# 41-SoC_POWER_SUPPLY.net
KiCad netlist of a schematic drawn in Altium Designer
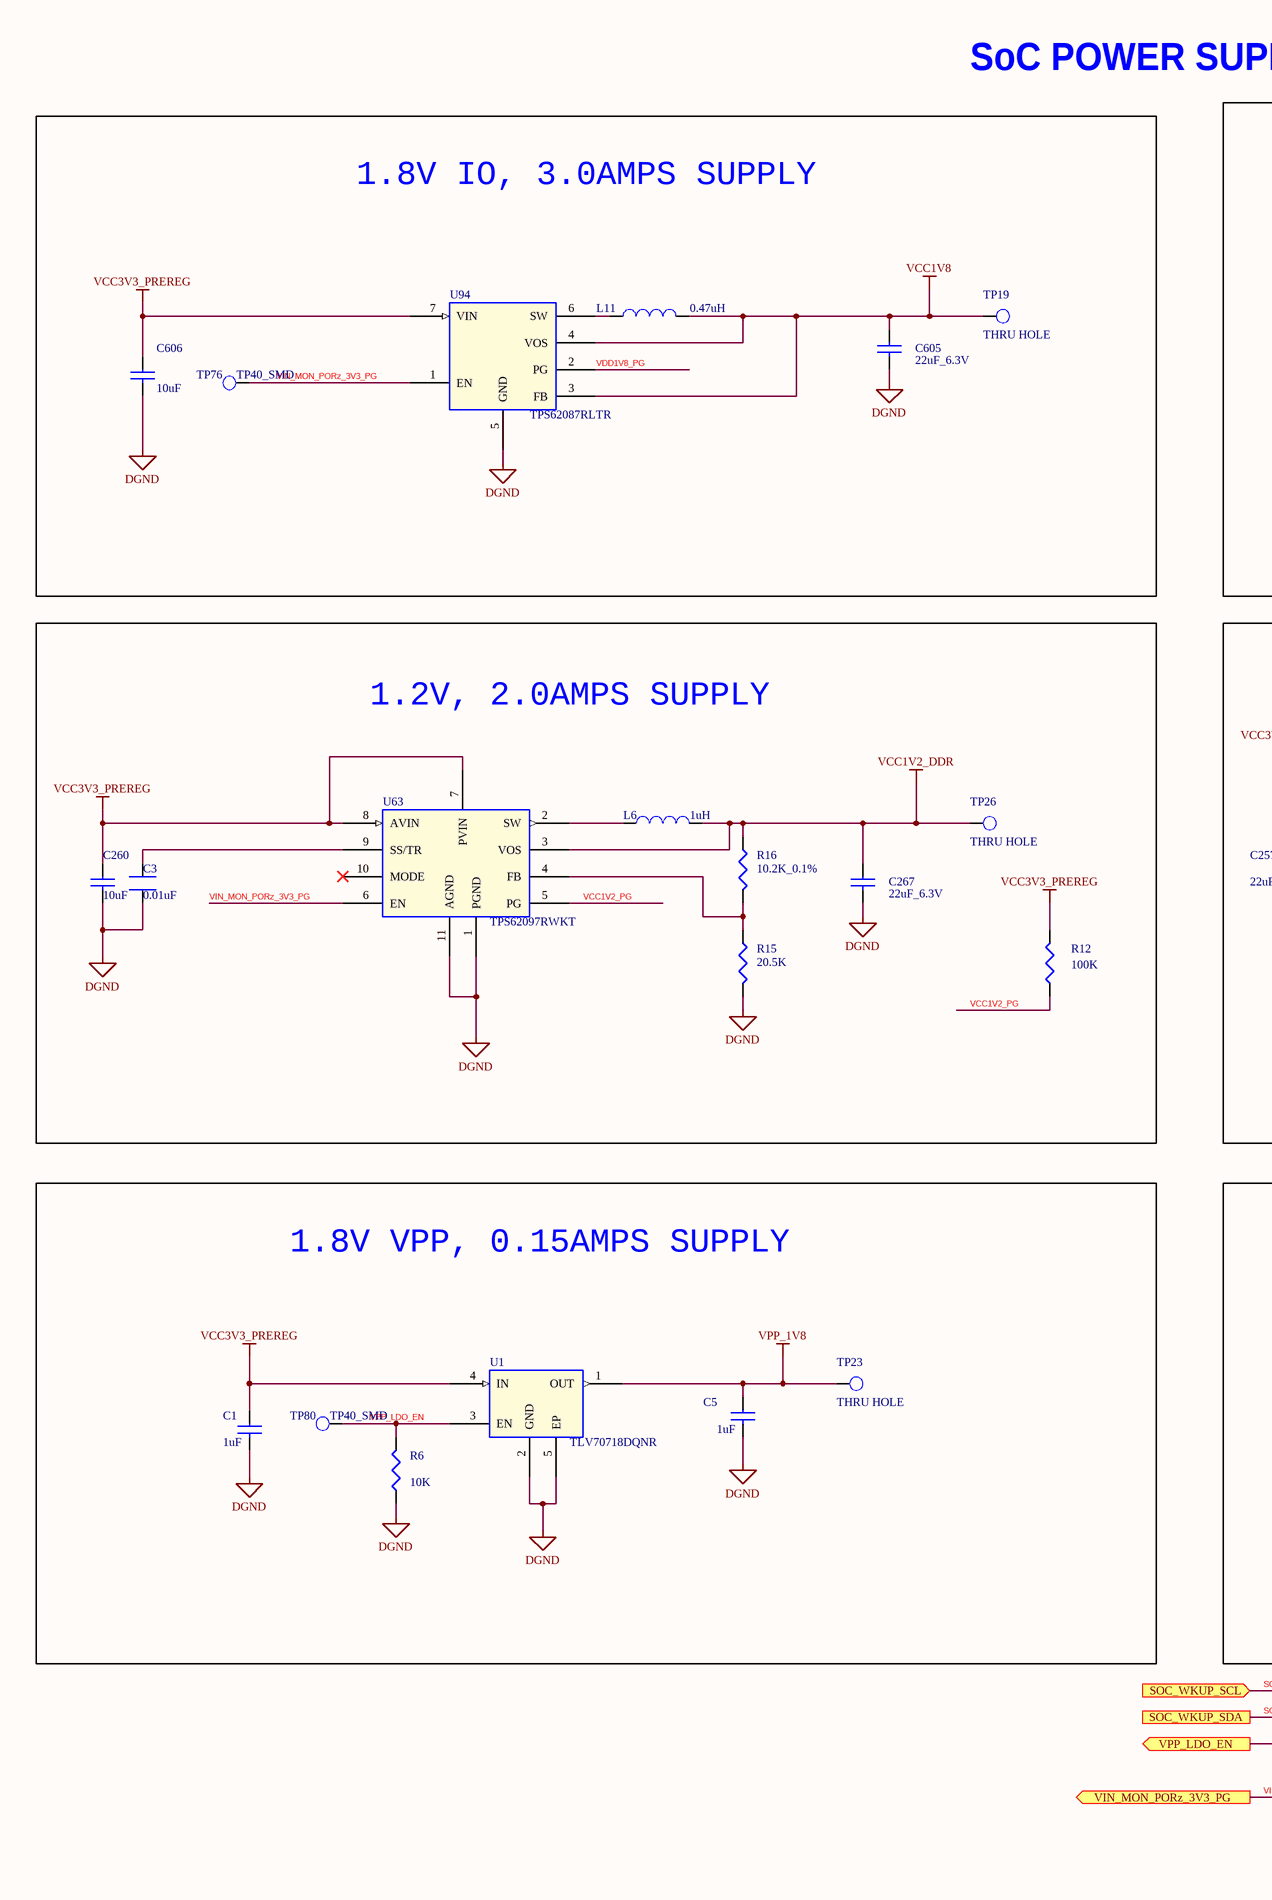
[diagram p0: 41-SoC POWER SUPPLY.SchDoc, left]
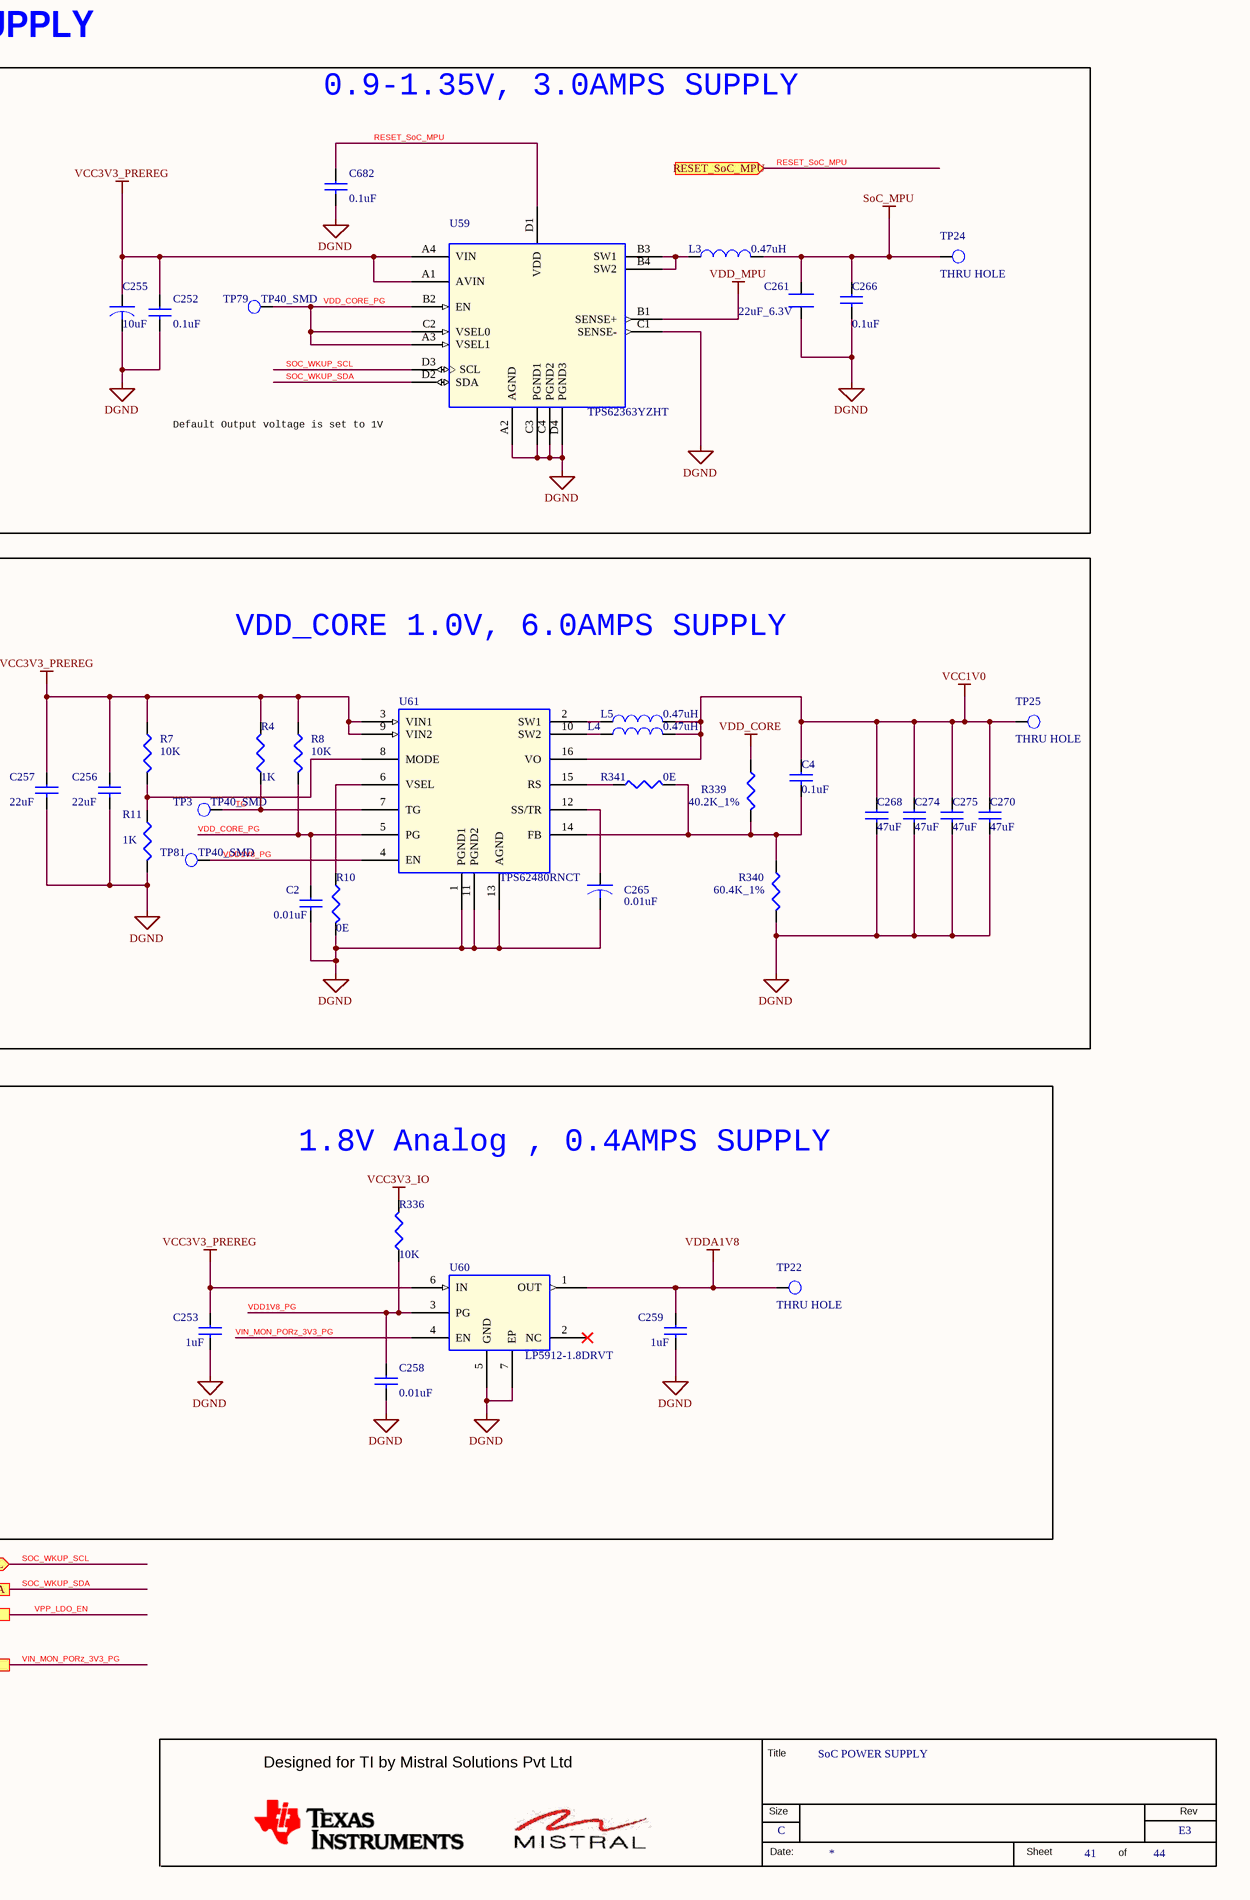
[diagram p1: 41-SoC POWER SUPPLY.SchDoc, right]

(export (version "E")
  (design (tool "Eeschema 10.0.6"))
  (components
    (comp (ref "C1")
      (value "1uF")
      (footprint "CAP0603_1")
      (description "CAP CERAMIC 1uF 25V 10% X5R 0603")
      (fields
        (field (name "MISTRAL PART NO") "120010080040-R")
        (field (name "MFR_PART_NUMBER") "06033D105KAT2A")
      )
      (libsource (lib "*") (part "CAP_Dup5"))
    )
    (comp (ref "C2")
      (value "0.01uF")
      (footprint "CAP0201_0-5")
      (description "CAP CERAMIC 0.01uF 25V 10% X5R 0201")
      (fields
        (field (name "MISTRAL PART NO") "120018010007-R")
        (field (name "MFR_PART_NUMBER") "GRM033R61E103KA12J")
      )
      (libsource (lib "*") (part "CAP_Dup5"))
    )
    (comp (ref "C3")
      (value "0.01uF")
      (footprint "TMDX654GPEVM_BRD:CAP0201_0-5")
      (description "CAP CERAMIC 0.01uF 25V 10% X5R 0201")
      (fields (field (name "DISTRIBUTOR_PART_NUMBER") "GRM033R61E103KA12J-ND") (field (name "VOLTAGE") "25V"))
      (libsource (lib "*") (part "CAP_Dup3"))
    )
    (comp (ref "C4")
      (value "0.1uF")
      (footprint "CAP0201_0-5")
      (description "CAP CERAMIC 0.1uF 16V 10% X5R 0201")
      (fields (field (name "DISTRIBUTOR_PART_NUMBER") "490-16742-1-ND") (field (name "VOLTAGE") "16V"))
      (libsource (lib "*") (part "CAP_Dup5"))
    )
    (comp (ref "C5")
      (value "1uF")
      (footprint "CAP0603_1")
      (description "CAP CERAMIC 1uF 25V 10% X5R 0603")
      (fields
        (field (name "MISTRAL PART NO") "120010080040-R")
        (field (name "MFR_PART_NUMBER") "06033D105KAT2A")
      )
      (libsource (lib "*") (part "CAP_Dup5"))
    )
    (comp (ref "C252")
      (value "0.1uF")
      (footprint "CAP0201_0-5")
      (description "CAP CERAMIC 0.1uF 16V 10% X5R 0201")
      (fields (field (name "DISTRIBUTOR_PART_NUMBER") "490-16742-1-ND") (field (name "VOLTAGE") "16V"))
      (libsource (lib "*") (part "CAP_Dup5"))
    )
    (comp (ref "C253")
      (value "1uF")
      (footprint "CAP0603_1")
      (description "CAP CERAMIC 1uF 25V 10% X5R 0603")
      (fields
        (field (name "MISTRAL PART NO") "120010080040-R")
        (field (name "MFR_PART_NUMBER") "06033D105KAT2A")
      )
      (libsource (lib "*") (part "CAP_Dup5"))
    )
    (comp (ref "C255")
      (value "10uF")
      (footprint "CAP1206_2")
      (description "CAP CERAMIC 10uF 50V 20% X5R 1206")
      (fields (field (name "DISTRIBUTOR_PART_NUMBER") "490-10756-1-ND") (field (name "VOLTAGE") "50V"))
      (libsource (lib "*") (part "CAP"))
    )
    (comp (ref "C256")
      (value "22uF")
      (footprint "CAP1206_2")
      (description "CAP CERAMIC 22uF 16V 20% X7R 1206")
      (fields
        (field (name "MISTRAL PART NO") "120017010003-R")
        (field (name "MFR_PART_NUMBER") "EMK316BB7226ML-T")
      )
      (libsource (lib "*") (part "CAP_Dup5"))
    )
    (comp (ref "C257")
      (value "22uF")
      (footprint "CAP1206_2")
      (description "CAP CERAMIC 22uF 16V 20% X7R 1206")
      (fields
        (field (name "MISTRAL PART NO") "120017010003-R")
        (field (name "MFR_PART_NUMBER") "EMK316BB7226ML-T")
      )
      (libsource (lib "*") (part "CAP_Dup5"))
    )
    (comp (ref "C258")
      (value "0.01uF")
      (footprint "CAP0201_0-5")
      (description "CAP CERAMIC 0.01uF 25V 10% X5R 0201")
      (fields (field (name "DISTRIBUTOR_PART_NUMBER") "GRM033R61E103KA12J-ND") (field (name "VOLTAGE") "25V"))
      (libsource (lib "*") (part "CAP_Dup5"))
    )
    (comp (ref "C259")
      (value "1uF")
      (footprint "CAP0603_1")
      (description "CAP CERAMIC 1uF 25V 10% X5R 0603")
      (fields
        (field (name "MISTRAL PART NO") "120010080040-R")
        (field (name "MFR_PART_NUMBER") "06033D105KAT2A")
      )
      (libsource (lib "*") (part "CAP_Dup5"))
    )
    (comp (ref "C260")
      (value "10uF")
      (footprint "CAP0603_1")
      (description "CAP CERAMIC 10uF 10V 10% X5R 0603")
      (fields
        (field (name "MISTRAL PART NO") "120010080001-R")
        (field (name "MFR_PART_NUMBER") "0603ZD106KAT2A")
      )
      (libsource (lib "*") (part "CAP_Dup5"))
    )
    (comp (ref "C261")
      (value "22uF_6.3V")
      (footprint "TMDX654GPEVM_BRD:CAP0603")
      (description "CAP CERAMIC 22uF 6.3V 20% X5R 0603")
      (fields
        (field (name "MISTRAL PART NO") "120015090007-R")
        (field (name "MFR_PART_NUMBER") "GRM188R60J226MEA0")
      )
      (libsource (lib "*") (part "CAP_Dup3"))
    )
    (comp (ref "C265")
      (value "0.01uF")
      (footprint "CAP0402_0-75")
      (description "CAP CERAMIC 0.01uF 10V 10% X7R 0402")
      (fields
        (field (name "MISTRAL PART NO") "120009030017-R")
        (field (name "MFR_PART_NUMBER") "0402ZC103KAT2A")
      )
      (libsource (lib "*") (part "CAP"))
    )
    (comp (ref "C266")
      (value "0.1uF")
      (footprint "CAP0201_0-5")
      (description "CAP CERAMIC 0.1uF 16V 10% X5R 0201")
      (fields
        (field (name "MISTRAL PART NO") "120009030072-R")
        (field (name "MFR_PART_NUMBER") "GRM033R61C104KE84J")
      )
      (libsource (lib "*") (part "CAP_Dup5"))
    )
    (comp (ref "C267")
      (value "22uF_6.3V")
      (footprint "CAP0603")
      (description "CAP CERAMIC 22uF 6.3V 20% X5R 0603")
      (fields (field (name "DISTRIBUTOR_PART_NUMBER") "490-7611-2-ND") (field (name "VOLTAGE") "6.3V"))
      (libsource (lib "*") (part "CAP_Dup5"))
    )
    (comp (ref "C268")
      (value "47uF")
      (footprint "CAP0603_1")
      (description "CAP CERAMIC 47uF 6.3V 20% X5R 0603")
      (fields (field (name "DISTRIBUTOR_PART_NUMBER") "490-13247-1-ND") (field (name "VOLTAGE") "6.3V"))
      (libsource (lib "*") (part "CAP_Dup5"))
    )
    (comp (ref "C270")
      (value "47uF")
      (footprint "CAP0603_1")
      (description "CAP CERAMIC 47uF 6.3V 20% X5R 0603")
      (fields
        (field (name "MISTRAL PART NO") "120016110001-R")
        (field (name "MFR_PART_NUMBER") "GRM188R60J476ME15D")
      )
      (libsource (lib "*") (part "CAP_Dup5"))
    )
    (comp (ref "C274")
      (value "47uF")
      (footprint "CAP0603_1")
      (description "CAP CERAMIC 47uF 6.3V 20% X5R 0603")
      (fields
        (field (name "MISTRAL PART NO") "120016110001-R")
        (field (name "MFR_PART_NUMBER") "GRM188R60J476ME15D")
      )
      (libsource (lib "*") (part "CAP_Dup5"))
    )
    (comp (ref "C275")
      (value "47uF")
      (footprint "CAP0603_1")
      (description "CAP CERAMIC 47uF 6.3V 20% X5R 0603")
      (fields
        (field (name "MISTRAL PART NO") "120016110001-R")
        (field (name "MFR_PART_NUMBER") "GRM188R60J476ME15D")
      )
      (libsource (lib "*") (part "CAP_Dup5"))
    )
    (comp (ref "C605")
      (value "22uF_6.3V")
      (footprint "CAP0603")
      (description "CAP CERAMIC 22uF 6.3V 20% X5R 0603")
      (fields
        (field (name "MISTRAL PART NO") "120015090007-R")
        (field (name "MFR_PART_NUMBER") "GRM188R60J226MEA0")
      )
      (libsource (lib "*") (part "CAP_Dup5"))
    )
    (comp (ref "C606")
      (value "10uF")
      (footprint "CAP1206_2")
      (description "CAP CERAMIC 10uF 16V 10% X7R 1206")
      (fields
        (field (name "MISTRAL PART NO") "120009090010-R")
        (field (name "MFR_PART_NUMBER") "C1206C106K4RACTU")
      )
      (libsource (lib "*") (part "CAP_Dup5"))
    )
    (comp (ref "C682")
      (value "0.1uF")
      (footprint "CAP0201_0-5")
      (description "CAP CERAMIC 0.1uF 16V 10% X5R 0201")
      (fields (field (name "DISTRIBUTOR_PART_NUMBER") "490-16742-1-ND") (field (name "VOLTAGE") "16V"))
      (libsource (lib "*") (part "CAP_Dup5"))
    )
    (comp (ref "L3")
      (value "0.47uH")
      (footprint "IND_XEL4030_170X170_SMD_1-6")
      (description "IND POWER 0.47uH 20% 11.2A SMD")
      (fields
        (field (name "MISTRAL PART NO") "130018020040-R")
        (field (name "MFR_PART_NUMBER") "XFL4015-471MEB")
      )
      (libsource (lib "*") (part "INDUCTOR"))
    )
    (comp (ref "L4")
      (value "0.47uH")
      (footprint "IND_XEL4030_170X170_SMD_1-6")
      (description "IND POWER 0.47uH 20% 11.2A SMD")
      (fields (field (name "DISTRIBUTOR_PART_NUMBER") "994-XFL4015-471MEB") (field (name "VOLTAGE") "NA"))
      (libsource (lib "*") (part "INDUCTOR"))
    )
    (comp (ref "L5")
      (value "0.47uH")
      (footprint "IND_XEL4030_170X170_SMD_1-6")
      (description "IND POWER 0.47uH 20% 11.2A SMD")
      (fields (field (name "DISTRIBUTOR_PART_NUMBER") "994-XFL4015-471MEB") (field (name "VOLTAGE") "NA"))
      (libsource (lib "*") (part "INDUCTOR"))
    )
    (comp (ref "L6")
      (value "1uH")
      (footprint "IND_IHLP2020AB_210X210_SMD_1-2")
      (description "IND POWER 1uH 4.4A 20% SMD")
      (fields (field (name "DISTRIBUTOR_PART_NUMBER") "541-1704-1-ND") (field (name "VOLTAGE") "NA"))
      (libsource (lib "*") (part "INDUCTOR"))
    )
    (comp (ref "L11")
      (value "0.47uH")
      (footprint "IND_XEL4030_170X170_SMD_1-6")
      (description "IND POWER 0.47uH 20% 11.2A SMD")
      (fields (field (name "DISTRIBUTOR_PART_NUMBER") "994-XFL4015-471MEB") (field (name "VOLTAGE") "NA"))
      (libsource (lib "*") (part "INDUCTOR"))
    )
    (comp (ref "R4")
      (value "1K")
      (footprint "RES0201")
      (description "RES 1K 1/20W 5% 0201")
      (fields
        (field (name "MISTRAL PART NO") "110015080014-R")
        (field (name "MFR_PART_NUMBER") "CRCW02011K00FKED")
      )
      (libsource (lib "*") (part "RESISTOR_Dup4"))
    )
    (comp (ref "R6")
      (value "10K")
      (footprint "RES0402_0-5")
      (description "RES 10K 1/16W 5% 0402")
      (fields (field (name "DISTRIBUTOR_PART_NUMBER") "311-10KJRCT-ND") (field (name "VOLTAGE") "NA"))
      (libsource (lib "*") (part "RESISTOR_Dup5"))
    )
    (comp (ref "R7")
      (value "10K")
      (footprint "RES0402_0-5")
      (description "RES 10K 1/16W 5% 0402")
      (fields (field (name "DISTRIBUTOR_PART_NUMBER") "311-10KJRCT-ND") (field (name "VOLTAGE") "NA"))
      (libsource (lib "*") (part "RESISTOR_Dup5"))
    )
    (comp (ref "R8")
      (value "10K")
      (footprint "RES0402_0-5")
      (description "RES 10K 1/16W 5% 0402")
      (fields
        (field (name "MISTRAL PART NO") "110009030208-R")
        (field (name "MFR_PART_NUMBER") "RC0402JR-0710KL")
      )
      (libsource (lib "*") (part "RESISTOR_Dup5"))
    )
    (comp (ref "R10")
      (value "0E")
      (footprint "RES0402_0-5")
      (description "RES 0E 1/16W 0402")
      (fields (field (name "DISTRIBUTOR_PART_NUMBER") "541-0.0JCT-ND") (field (name "VOLTAGE") "NA"))
      (libsource (lib "*") (part "RESISTOR_Dup5"))
    )
    (comp (ref "R11")
      (value "1K")
      (footprint "RES0201")
      (description "RES 1K 1/20W 5% 0201")
      (fields
        (field (name "MISTRAL PART NO") "110015080014-R")
        (field (name "MFR_PART_NUMBER") "CRCW02011K00FKED")
      )
      (libsource (lib "*") (part "RESISTOR_Dup5"))
    )
    (comp (ref "R12")
      (value "100K")
      (footprint "RES0402_0-5")
      (description "RES 100K 1/16W 5% 0402")
      (fields (field (name "DISTRIBUTOR_PART_NUMBER") "541-100KJCT-ND") (field (name "VOLTAGE") "NA"))
      (libsource (lib "*") (part "RESISTOR_Dup5"))
    )
    (comp (ref "R15")
      (value "20.5K")
      (footprint "RES0402")
      (description "RES 20.5K 1/10W 1% 0402")
      (fields
        (field (name "MISTRAL PART NO") "110010090063-R")
        (field (name "MFR_PART_NUMBER") "ERJ-2RKF2052X")
      )
      (libsource (lib "*") (part "RESISTOR_Dup5"))
    )
    (comp (ref "R16")
      (value "10.2K_0.1%")
      (footprint "RES0402")
      (description "RES 10.2K 1/16W 0.1% 0402")
      (fields
        (field (name "MISTRAL PART NO") "110011050017-R")
        (field (name "MFR_PART_NUMBER") "TNPW040210K2BEED")
      )
      (libsource (lib "*") (part "RESISTOR_Dup5"))
    )
    (comp (ref "R336")
      (value "10K")
      (footprint "RES0402_0-5")
      (description "RES 10K 1/16W 5% 0402")
      (fields
        (field (name "MISTRAL PART NO") "110009030208-R")
        (field (name "MFR_PART_NUMBER") "RC0402JR-0710KL")
      )
      (libsource (lib "*") (part "RESISTOR_Dup5"))
    )
    (comp (ref "R339")
      (value "40.2K_1%")
      (footprint "RES0402_0-5")
      (description "RES 40.2K 1/16W 1% 0402")
      (fields
        (field (name "MISTRAL PART NO") "110009030811")
        (field (name "MFR_PART_NUMBER") "RC0402FR-0740K2L")
      )
      (libsource (lib "*") (part "RESISTOR_Dup5"))
    )
    (comp (ref "R340")
      (value "60.4K_1%")
      (footprint "RES0402_0-5")
      (description "RES 60.4K 1/16W 1% 0402")
      (fields
        (field (name "MISTRAL PART NO") "110012110012-R")
        (field (name "MFR_PART_NUMBER") "RC0402FR-0760K4L")
      )
      (libsource (lib "*") (part "RESISTOR_Dup5"))
    )
    (comp (ref "R341")
      (value "0E")
      (footprint "RES0402_0-5")
      (description "RES 0E 1/16W 0402")
      (fields
        (field (name "MISTRAL PART NO") "110010080019-P")
        (field (name "MFR_PART_NUMBER") "CRCW04020000Z0ED")
      )
      (libsource (lib "*") (part "RESISTOR_Dup5"))
    )
    (comp (ref "TP3")
      (value "TP40_SMD")
      (footprint "TP40_SMD")
      (description "TESTPOINT CIR 40 SMD")
      (fields (field (name "VOLTAGE") "NA") (field (name "MISTRAL PART NO") "130009030933"))
      (libsource (lib "*") (part "TESTPOINT"))
    )
    (comp (ref "TP19")
      (value "THRU HOLE")
      (footprint "TP_40X65")
      (description "TESTPOINT 1.0MM DRILL PTH")
      (fields (field (name "MISTRAL PART NO") "130009030938") (field (name "MFR_PART_NUMBER") "TP_40X65"))
      (libsource (lib "*") (part "TESTPOINT"))
    )
    (comp (ref "TP22")
      (value "THRU HOLE")
      (footprint "TP_40X65")
      (description "TESTPOINT 1.0MM DRILL PTH")
      (fields (field (name "MISTRAL PART NO") "130009030938") (field (name "MFR_PART_NUMBER") "TP_40X65"))
      (libsource (lib "*") (part "TESTPOINT"))
    )
    (comp (ref "TP23")
      (value "THRU HOLE")
      (footprint "TP_40X65")
      (description "TESTPOINT 1.0MM DRILL PTH")
      (fields (field (name "MISTRAL PART NO") "130009030938") (field (name "MFR_PART_NUMBER") "TP_40X65"))
      (libsource (lib "*") (part "TESTPOINT"))
    )
    (comp (ref "TP24")
      (value "THRU HOLE")
      (footprint "TP_40X65")
      (description "TESTPOINT 1.0MM DRILL PTH")
      (fields (field (name "MISTRAL PART NO") "130009030938") (field (name "MFR_PART_NUMBER") "TP_40X65"))
      (libsource (lib "*") (part "TESTPOINT"))
    )
    (comp (ref "TP25")
      (value "THRU HOLE")
      (footprint "TP_40X65")
      (description "TESTPOINT 1.0MM DRILL PTH")
      (fields (field (name "MISTRAL PART NO") "130009030938") (field (name "MFR_PART_NUMBER") "TP_40X65"))
      (libsource (lib "*") (part "TESTPOINT"))
    )
    (comp (ref "TP26")
      (value "THRU HOLE")
      (footprint "TP_40X65")
      (description "TESTPOINT 1.0MM DRILL PTH")
      (fields (field (name "MISTRAL PART NO") "130009030938") (field (name "MFR_PART_NUMBER") "TP_40X65"))
      (libsource (lib "*") (part "TESTPOINT"))
    )
    (comp (ref "TP76")
      (value "TP40_SMD")
      (footprint "TP40_SMD")
      (description "TESTPOINT CIR 40 SMD")
      (fields (field (name "VOLTAGE") "NA") (field (name "MISTRAL PART NO") "130009030933"))
      (libsource (lib "*") (part "TESTPOINT"))
    )
    (comp (ref "TP79")
      (value "TP40_SMD")
      (footprint "TP40_SMD")
      (description "TESTPOINT CIR 40 SMD")
      (fields (field (name "MISTRAL PART NO") "130009030933") (field (name "DISTRIBUTOR_PART_NUMBER") "NA"))
      (libsource (lib "*") (part "TESTPOINT"))
    )
    (comp (ref "TP80")
      (value "TP40_SMD")
      (footprint "TP40_SMD")
      (description "TESTPOINT CIR 40 SMD")
      (fields (field (name "VOLTAGE") "NA") (field (name "MISTRAL PART NO") "130009030933"))
      (libsource (lib "*") (part "TESTPOINT"))
    )
    (comp (ref "TP81")
      (value "TP40_SMD")
      (footprint "TP40_SMD")
      (description "TESTPOINT CIR 40 SMD")
      (fields (field (name "VOLTAGE") "NA") (field (name "MISTRAL PART NO") "130009030933"))
      (libsource (lib "*") (part "TESTPOINT"))
    )
    (comp (ref "U1")
      (value "TLV70718DQNR")
      (footprint "X2SON4_TLV71318P_40X40_0-4")
      (description "IC 200mA LOW IQ LOW NOISE LDO REGULATOR X2SON-4")
      (fields
        (field (name "DISTRIBUTOR_PART_NUMBER") "296-36768-1-ND")
        (field (name "VOLTAGE") "NA")
        (field (name "LIBRARY PATH") "Y~{:}MIS_DATABAS~{E}Librar~{y}ALTIUM_TOO~{L}SCHEMATICS_PART~{S}MS_MISCPOWER_Library.schlib")
      )
      (libsource (lib "*") (part "TLV71318PDQNR_X2SON4"))
    )
    (comp (ref "U59")
      (value "TPS62363YZHT")
      (footprint "DSBGA16_19-68_80X80_0-7")
      (description "IC 3A PROCESSOR SUPPLY WITH I2C INTERFACE DSBGA16")
      (fields (field (name "DISTRIBUTOR_PART_NUMBER") "296-30361-1-ND") (field (name "VOLTAGE") "NA"))
      (libsource (lib "*") (part "TPS6236X_DSBGA16"))
    )
    (comp (ref "U60")
      (value "LP5912-1.8DRVT")
      (footprint "SON6_25-59_85X85_0-8")
      (description "IC 500mA LOW NOISE LOW IQ LDO WSON6")
      (fields (field (name "MISTRAL PART NO") "142017090021-R") (field (name "TOLERANCE") "NA"))
      (libsource (lib "*") (part "LP5912-1-8DRVT_WSON6"))
    )
    (comp (ref "U61")
      (value "TPS62480RNCT")
      (footprint "VQFNHR16_TPS62480_100X120_1")
      (description "IC 2-PHASE STEP DOWN DC-DC CONVERTER VQFN-HR16")
      (fields (field (name "MISTRAL PART NO") "142017090012-R") (field (name "TOLERANCE") "NA"))
      (libsource (lib "*") (part "TPS62480RNCT_VQFNHR16"))
    )
    (comp (ref "U63")
      (value "TPS62097RWKT")
      (footprint "VQFNHR11_TPS62097_80X80_1")
      (description "IC 2A SYNCHRONOUS STEP DOWN CONVERTER WITH IDCS CONTROL VQFN-HR11")
      (fields (field (name "DISTRIBUTOR_PART_NUMBER") "296-43330-1-ND") (field (name "VOLTAGE") "NA"))
      (libsource (lib "*") (part "TPS62097RWKT_VQFNHR11"))
    )
    (comp (ref "U94")
      (value "TPS62087RLTR")
      (footprint "VSONHR7_TPS62085_80X80_1")
      (description "IC 3A STEP DOWN CONVERTER WITH SHORT CIRCUIT PROTECTION VSON-HR7")
      (fields (field (name "DISTRIBUTOR_PART_NUMBER") "296-40832-1-ND") (field (name "VOLTAGE") "NA"))
      (libsource (lib "*") (part "TPS62085RLTR_VSONHR7"))
    )
  )
  (nets
    (net (code "1") (name "/RESET_SoC_MPU") (class "Default")
      (node (ref "C682") (pin "1") (pinfunction "1_1") (pintype "passive"))
      (node (ref "U59") (pin "D1") (pinfunction "VDD_D1") (pintype "power_in"))
    )
    (net (code "2") (name "/SOC_WKUP_SCL") (class "Default")
      (node (ref "U59") (pin "D3") (pinfunction "SCL_D3") (pintype "bidirectional"))
    )
    (net (code "3") (name "/SOC_WKUP_SDA") (class "Default")
      (node (ref "U59") (pin "D2") (pinfunction "SDA_D2") (pintype "bidirectional"))
    )
    (net (code "4") (name "/TG") (class "Default")
      (node (ref "R4") (pin "1") (pinfunction "1_1") (pintype "passive"))
      (node (ref "TP3") (pin "1") (pinfunction "TP_1") (pintype "passive"))
      (node (ref "U61") (pin "7") (pinfunction "TG_7") (pintype "passive"))
    )
    (net (code "5") (name "/VCC1V2_PG") (class "Default")
      (node (ref "R12") (pin "1") (pinfunction "1_1") (pintype "passive"))
      (node (ref "U63") (pin "5") (pinfunction "PG_5") (pintype "passive"))
    )
    (net (code "6") (name "/VDD1V8_PG") (class "Default")
      (node (ref "C258") (pin "1") (pinfunction "1_1") (pintype "passive"))
      (node (ref "R336") (pin "1") (pinfunction "1_1") (pintype "passive"))
      (node (ref "TP81") (pin "1") (pinfunction "TP_1") (pintype "passive"))
      (node (ref "U60") (pin "3") (pinfunction "PG_3") (pintype "passive"))
      (node (ref "U61") (pin "4") (pinfunction "EN_4") (pintype "passive"))
      (node (ref "U94") (pin "2") (pinfunction "PG_2") (pintype "passive"))
    )
    (net (code "7") (name "/VDD_CORE_PG") (class "Default")
      (node (ref "C2") (pin "1") (pinfunction "1_1") (pintype "passive"))
      (node (ref "R8") (pin "2") (pinfunction "2_2") (pintype "passive"))
      (node (ref "TP79") (pin "1") (pinfunction "TP_1") (pintype "passive"))
      (node (ref "U59") (pin "A3") (pinfunction "VSEL1_A3") (pintype "input"))
      (node (ref "U59") (pin "B2") (pinfunction "EN_B2") (pintype "input"))
      (node (ref "U59") (pin "C2") (pinfunction "VSEL0_C2") (pintype "input"))
      (node (ref "U61") (pin "5") (pinfunction "PG_5") (pintype "passive"))
    )
    (net (code "8") (name "/VIN_MON_PORz_3V3_PG") (class "Default")
      (node (ref "TP76") (pin "1") (pinfunction "TP_1") (pintype "passive"))
      (node (ref "U60") (pin "4") (pinfunction "EN_4") (pintype "passive"))
      (node (ref "U63") (pin "6") (pinfunction "EN_6") (pintype "passive"))
      (node (ref "U94") (pin "1") (pinfunction "EN_1") (pintype "passive"))
    )
    (net (code "9") (name "/VPP_LDO_EN") (class "Default")
      (node (ref "R6") (pin "2") (pinfunction "2_2") (pintype "passive"))
      (node (ref "TP80") (pin "1") (pinfunction "TP_1") (pintype "passive"))
      (node (ref "U1") (pin "3") (pinfunction "EN_3") (pintype "passive"))
    )
    (net (code "10") (name "DGND") (class "Default")
      (node (ref "C1") (pin "2") (pinfunction "2_2") (pintype "passive"))
      (node (ref "C2") (pin "2") (pinfunction "2_2") (pintype "passive"))
      (node (ref "C252") (pin "2") (pinfunction "2_2") (pintype "passive"))
      (node (ref "C253") (pin "2") (pinfunction "2_2") (pintype "passive"))
      (node (ref "C255") (pin "2") (pinfunction "2_2") (pintype "passive"))
      (node (ref "C256") (pin "2") (pinfunction "2_2") (pintype "passive"))
      (node (ref "C257") (pin "2") (pinfunction "2_2") (pintype "passive"))
      (node (ref "C258") (pin "2") (pinfunction "2_2") (pintype "passive"))
      (node (ref "C259") (pin "2") (pinfunction "2_2") (pintype "passive"))
      (node (ref "C260") (pin "2") (pinfunction "2_2") (pintype "passive"))
      (node (ref "C261") (pin "2") (pinfunction "2_2") (pintype "passive"))
      (node (ref "C265") (pin "2") (pinfunction "2_2") (pintype "passive"))
      (node (ref "C266") (pin "2") (pinfunction "2_2") (pintype "passive"))
      (node (ref "C267") (pin "2") (pinfunction "2_2") (pintype "passive"))
      (node (ref "C268") (pin "2") (pinfunction "2_2") (pintype "passive"))
      (node (ref "C270") (pin "2") (pinfunction "2_2") (pintype "passive"))
      (node (ref "C274") (pin "2") (pinfunction "2_2") (pintype "passive"))
      (node (ref "C275") (pin "2") (pinfunction "2_2") (pintype "passive"))
      (node (ref "C3") (pin "2") (pinfunction "2_2") (pintype "passive"))
      (node (ref "C5") (pin "2") (pinfunction "2_2") (pintype "passive"))
      (node (ref "C605") (pin "2") (pinfunction "2_2") (pintype "passive"))
      (node (ref "C606") (pin "2") (pinfunction "2_2") (pintype "passive"))
      (node (ref "C682") (pin "2") (pinfunction "2_2") (pintype "passive"))
      (node (ref "R10") (pin "2") (pinfunction "2_2") (pintype "passive"))
      (node (ref "R11") (pin "2") (pinfunction "2_2") (pintype "passive"))
      (node (ref "R15") (pin "2") (pinfunction "2_2") (pintype "passive"))
      (node (ref "R340") (pin "2") (pinfunction "2_2") (pintype "passive"))
      (node (ref "R6") (pin "1") (pinfunction "1_1") (pintype "passive"))
      (node (ref "U1") (pin "2") (pinfunction "GND_2") (pintype "power_in"))
      (node (ref "U1") (pin "5") (pinfunction "EP_5") (pintype "power_in"))
      (node (ref "U59") (pin "A2") (pinfunction "AGND_A2") (pintype "power_in"))
      (node (ref "U59") (pin "C1") (pinfunction "SENSE-_C1") (pintype "output"))
      (node (ref "U59") (pin "C3") (pinfunction "PGND1_C3") (pintype "power_in"))
      (node (ref "U59") (pin "C4") (pinfunction "PGND2_C4") (pintype "power_in"))
      (node (ref "U59") (pin "D4") (pinfunction "PGND3_D4") (pintype "power_in"))
      (node (ref "U60") (pin "5") (pinfunction "GND_5") (pintype "power_in"))
      (node (ref "U60") (pin "7") (pinfunction "EP_7") (pintype "power_in"))
      (node (ref "U61") (pin "1") (pinfunction "PGND1_1") (pintype "power_in"))
      (node (ref "U61") (pin "11") (pinfunction "PGND2_11") (pintype "power_in"))
      (node (ref "U61") (pin "13") (pinfunction "AGND_13") (pintype "power_in"))
      (node (ref "U63") (pin "1") (pinfunction "PGND_1") (pintype "power_in"))
      (node (ref "U63") (pin "11") (pinfunction "AGND_11") (pintype "power_in"))
      (node (ref "U94") (pin "5") (pinfunction "GND_5") (pintype "power_in"))
    )
    (net (code "11") (name "Net-(U59-SW1)") (class "Default")
      (node (ref "L3") (pin "1") (pinfunction "1_1") (pintype "passive"))
      (node (ref "U59") (pin "B3") (pinfunction "SW1_B3") (pintype "passive"))
      (node (ref "U59") (pin "B4") (pinfunction "SW2_B4") (pintype "passive"))
    )
    (net (code "12") (name "Net-(U61-FB)") (class "Default")
      (node (ref "C4") (pin "2") (pinfunction "2_2") (pintype "passive"))
      (node (ref "R339") (pin "2") (pinfunction "2_2") (pintype "passive"))
      (node (ref "R340") (pin "1") (pinfunction "1_1") (pintype "passive"))
      (node (ref "R341") (pin "2") (pinfunction "2_2") (pintype "passive"))
      (node (ref "U61") (pin "14") (pinfunction "FB_14") (pintype "passive"))
    )
    (net (code "13") (name "Net-(U61-MODE)") (class "Default")
      (node (ref "R11") (pin "1") (pinfunction "1_1") (pintype "passive"))
      (node (ref "R7") (pin "2") (pinfunction "2_2") (pintype "passive"))
      (node (ref "U61") (pin "8") (pinfunction "MODE_8") (pintype "passive"))
    )
    (net (code "14") (name "Net-(U61-RS)") (class "Default")
      (node (ref "R341") (pin "1") (pinfunction "1_1") (pintype "passive"))
      (node (ref "U61") (pin "15") (pinfunction "RS_15") (pintype "passive"))
    )
    (net (code "15") (name "Net-(U61-SS{slash}TR)") (class "Default")
      (node (ref "C265") (pin "1") (pinfunction "1_1") (pintype "passive"))
      (node (ref "U61") (pin "12") (pinfunction "SS/TR_12") (pintype "passive"))
    )
    (net (code "16") (name "Net-(U61-SW1)") (class "Default")
      (node (ref "L5") (pin "1") (pinfunction "1_1") (pintype "passive"))
      (node (ref "U61") (pin "2") (pinfunction "SW1_2") (pintype "passive"))
    )
    (net (code "17") (name "Net-(U61-SW2)") (class "Default")
      (node (ref "L4") (pin "1") (pinfunction "1_1") (pintype "passive"))
      (node (ref "U61") (pin "10") (pinfunction "SW2_10") (pintype "passive"))
    )
    (net (code "18") (name "Net-(U61-VSEL)") (class "Default")
      (node (ref "R10") (pin "1") (pinfunction "1_1") (pintype "passive"))
      (node (ref "U61") (pin "6") (pinfunction "VSEL_6") (pintype "passive"))
    )
    (net (code "19") (name "Net-(U63-FB)") (class "Default")
      (node (ref "R15") (pin "1") (pinfunction "1_1") (pintype "passive"))
      (node (ref "R16") (pin "2") (pinfunction "2_2") (pintype "passive"))
      (node (ref "U63") (pin "4") (pinfunction "FB_4") (pintype "passive"))
    )
    (net (code "20") (name "Net-(U63-SS{slash}TR)") (class "Default")
      (node (ref "C3") (pin "1") (pinfunction "1_1") (pintype "passive"))
      (node (ref "U63") (pin "9") (pinfunction "SS/TR_9") (pintype "passive"))
    )
    (net (code "21") (name "Net-(U63-SW)") (class "Default")
      (node (ref "L6") (pin "1") (pinfunction "1_1") (pintype "passive"))
      (node (ref "U63") (pin "2") (pinfunction "SW_2") (pintype "output"))
    )
    (net (code "22") (name "Net-(U94-SW)") (class "Default")
      (node (ref "L11") (pin "1") (pinfunction "1_1") (pintype "passive"))
      (node (ref "U94") (pin "6") (pinfunction "SW_6") (pintype "passive"))
    )
    (net (code "23") (name "SoC_MPU") (class "Default")
      (node (ref "C261") (pin "1") (pinfunction "1_1") (pintype "passive"))
      (node (ref "C266") (pin "1") (pinfunction "1_1") (pintype "passive"))
      (node (ref "L3") (pin "2") (pinfunction "2_2") (pintype "passive"))
      (node (ref "TP24") (pin "1") (pinfunction "TP_1") (pintype "passive"))
    )
    (net (code "24") (name "VCC1V0") (class "Default")
      (node (ref "C268") (pin "1") (pinfunction "1_1") (pintype "passive"))
      (node (ref "C270") (pin "1") (pinfunction "1_1") (pintype "passive"))
      (node (ref "C274") (pin "1") (pinfunction "1_1") (pintype "passive"))
      (node (ref "C275") (pin "1") (pinfunction "1_1") (pintype "passive"))
      (node (ref "C4") (pin "1") (pinfunction "1_1") (pintype "passive"))
      (node (ref "L4") (pin "2") (pinfunction "2_2") (pintype "passive"))
      (node (ref "L5") (pin "2") (pinfunction "2_2") (pintype "passive"))
      (node (ref "TP25") (pin "1") (pinfunction "TP_1") (pintype "passive"))
      (node (ref "U61") (pin "16") (pinfunction "VO_16") (pintype "passive"))
    )
    (net (code "25") (name "VCC1V2_DDR") (class "Default")
      (node (ref "C267") (pin "1") (pinfunction "1_1") (pintype "passive"))
      (node (ref "L6") (pin "2") (pinfunction "2_2") (pintype "passive"))
      (node (ref "R16") (pin "1") (pinfunction "1_1") (pintype "passive"))
      (node (ref "TP26") (pin "1") (pinfunction "TP_1") (pintype "passive"))
      (node (ref "U63") (pin "3") (pinfunction "VOS_3") (pintype "passive"))
    )
    (net (code "26") (name "VCC1V8") (class "Default")
      (node (ref "C605") (pin "1") (pinfunction "1_1") (pintype "passive"))
      (node (ref "L11") (pin "2") (pinfunction "2_2") (pintype "passive"))
      (node (ref "TP19") (pin "1") (pinfunction "TP_1") (pintype "passive"))
      (node (ref "U94") (pin "3") (pinfunction "FB_3") (pintype "passive"))
      (node (ref "U94") (pin "4") (pinfunction "VOS_4") (pintype "passive"))
    )
    (net (code "27") (name "VCC3V3_IO") (class "Default")
      (node (ref "R336") (pin "2") (pinfunction "2_2") (pintype "passive"))
    )
    (net (code "28") (name "VCC3V3_PREREG") (class "Default")
      (node (ref "C1") (pin "1") (pinfunction "1_1") (pintype "passive"))
      (node (ref "C252") (pin "1") (pinfunction "1_1") (pintype "passive"))
      (node (ref "C253") (pin "1") (pinfunction "1_1") (pintype "passive"))
      (node (ref "C255") (pin "1") (pinfunction "1_1") (pintype "passive"))
      (node (ref "C256") (pin "1") (pinfunction "1_1") (pintype "passive"))
      (node (ref "C257") (pin "1") (pinfunction "1_1") (pintype "passive"))
      (node (ref "C260") (pin "1") (pinfunction "1_1") (pintype "passive"))
      (node (ref "C606") (pin "1") (pinfunction "1_1") (pintype "passive"))
      (node (ref "R12") (pin "2") (pinfunction "2_2") (pintype "passive"))
      (node (ref "R4") (pin "2") (pinfunction "2_2") (pintype "passive"))
      (node (ref "R7") (pin "1") (pinfunction "1_1") (pintype "passive"))
      (node (ref "R8") (pin "1") (pinfunction "1_1") (pintype "passive"))
      (node (ref "U1") (pin "4") (pinfunction "IN_4") (pintype "input"))
      (node (ref "U59") (pin "A1") (pinfunction "AVIN_A1") (pintype "power_in"))
      (node (ref "U59") (pin "A4") (pinfunction "VIN_A4") (pintype "power_in"))
      (node (ref "U60") (pin "6") (pinfunction "IN_6") (pintype "input"))
      (node (ref "U61") (pin "3") (pinfunction "VIN1_3") (pintype "input"))
      (node (ref "U61") (pin "9") (pinfunction "VIN2_9") (pintype "input"))
      (node (ref "U63") (pin "7") (pinfunction "PVIN_7") (pintype "power_in"))
      (node (ref "U63") (pin "8") (pinfunction "AVIN_8") (pintype "input"))
      (node (ref "U94") (pin "7") (pinfunction "VIN_7") (pintype "input"))
    )
    (net (code "29") (name "VDDA1V8") (class "Default")
      (node (ref "C259") (pin "1") (pinfunction "1_1") (pintype "passive"))
      (node (ref "TP22") (pin "1") (pinfunction "TP_1") (pintype "passive"))
      (node (ref "U60") (pin "1") (pinfunction "OUT_1") (pintype "output"))
    )
    (net (code "30") (name "VDD_CORE") (class "Default")
      (node (ref "R339") (pin "1") (pinfunction "1_1") (pintype "passive"))
    )
    (net (code "31") (name "VDD_MPU") (class "Default")
      (node (ref "U59") (pin "B1") (pinfunction "SENSE+_B1") (pintype "output"))
    )
    (net (code "32") (name "VPP_1V8") (class "Default")
      (node (ref "C5") (pin "1") (pinfunction "1_1") (pintype "passive"))
      (node (ref "TP23") (pin "1") (pinfunction "TP_1") (pintype "passive"))
      (node (ref "U1") (pin "1") (pinfunction "OUT_1") (pintype "output"))
    )
    (net (code "33") (name "unconnected-(U60-NC-Pad2)") (class "Default")
      (node (ref "U60") (pin "2") (pinfunction "NC_2") (pintype "passive+no_connect"))
    )
    (net (code "34") (name "unconnected-(U63-MODE-Pad10)") (class "Default")
      (node (ref "U63") (pin "10") (pinfunction "MODE_10") (pintype "passive+no_connect"))
    )
  )
)
